# Amazing-All-Band-Receiver.net
KiCad netlist of a schematic drawn in EAGLE
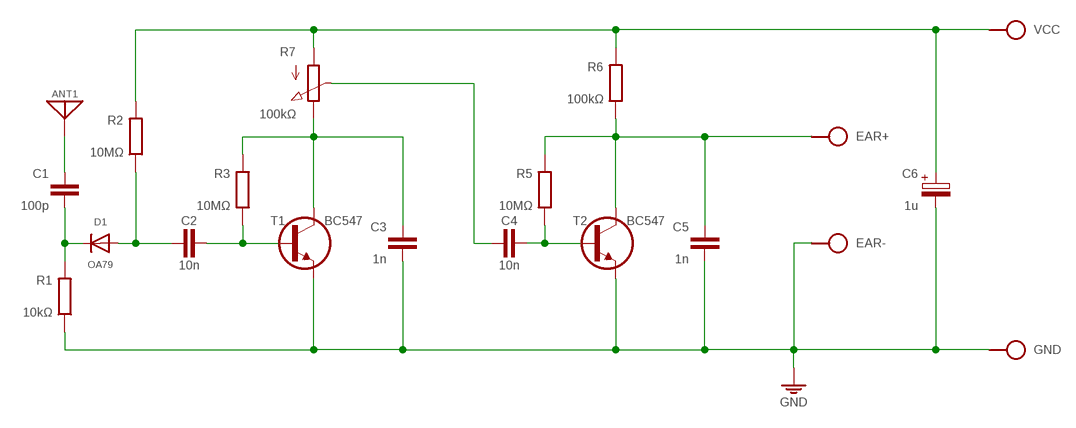
[diagram p0: schematic, sheet 1]

(export (version "E")
  (design (tool "Eeschema 10.0.6"))
  (components
    (comp (ref "ANT1")
      (value "ANT")
      (footprint "eagle-import:SPAD")
      (libsource (lib "eagle-import") (part "ANT"))
    )
    (comp (ref "C1")
      (value "100p")
      (footprint "eagle-import:C050-020X036_V")
      (libsource (lib "eagle-import") (part "C050-020X036/V"))
    )
    (comp (ref "C2")
      (value "10n")
      (footprint "eagle-import:C050-020X036")
      (libsource (lib "eagle-import") (part "C050-020X036"))
    )
    (comp (ref "C3")
      (value "1n")
      (footprint "eagle-import:C050-020X036")
      (libsource (lib "eagle-import") (part "C050-020X036"))
    )
    (comp (ref "C4")
      (value "10n")
      (footprint "eagle-import:C050-020X036")
      (libsource (lib "eagle-import") (part "C050-020X036"))
    )
    (comp (ref "C5")
      (value "1n")
      (footprint "eagle-import:C050-020X036")
      (libsource (lib "eagle-import") (part "C050-020X036"))
    )
    (comp (ref "C6")
      (value "1u")
      (footprint "eagle-import:E2,5-3")
      (libsource (lib "eagle-import") (part "CPOLE2,5-3"))
    )
    (comp (ref "D1")
      (value "OA79")
      (footprint "eagle-import:DO34-7V")
      (libsource (lib "eagle-import") (part "1N414834-7V"))
    )
    (comp (ref "EAR+")
      (value "SPAD")
      (footprint "eagle-import:SPAD")
      (libsource (lib "eagle-import") (part "SPAD"))
    )
    (comp (ref "EAR-")
      (value "SPAD")
      (footprint "eagle-import:SPAD")
      (libsource (lib "eagle-import") (part "SPAD"))
    )
    (comp (ref "GND")
      (value "SPAD")
      (footprint "eagle-import:SPAD")
      (libsource (lib "eagle-import") (part "SPAD"))
    )
    (comp (ref "R1")
      (value "10kΩ")
      (footprint "eagle-import:0202_7-V")
      (libsource (lib "eagle-import") (part "R0202/7-V"))
    )
    (comp (ref "R2")
      (value "10MΩ")
      (footprint "eagle-import:0202_7")
      (libsource (lib "eagle-import") (part "R0202/7"))
    )
    (comp (ref "R3")
      (value "10MΩ")
      (footprint "eagle-import:0202_7-V")
      (libsource (lib "eagle-import") (part "R0202/7-V"))
    )
    (comp (ref "R5")
      (value "10MΩ")
      (footprint "eagle-import:0202_7-V")
      (libsource (lib "eagle-import") (part "R0202/7-V"))
    )
    (comp (ref "R6")
      (value "100kΩ")
      (footprint "eagle-import:0202_7-V")
      (libsource (lib "eagle-import") (part "R0202/7-V"))
    )
    (comp (ref "R7")
      (value "100kΩ")
      (footprint "eagle-import:POT")
      (libsource (lib "eagle-import") (part "POT"))
    )
    (comp (ref "T1")
      (value "BC547")
      (footprint "eagle-import:TO92-CBE")
      (libsource (lib "eagle-import") (part "BC547CBE"))
    )
    (comp (ref "T2")
      (value "BC547")
      (footprint "eagle-import:TO92-CBE")
      (libsource (lib "eagle-import") (part "BC547CBE"))
    )
    (comp (ref "VCC")
      (value "SPAD")
      (footprint "eagle-import:SPAD")
      (libsource (lib "eagle-import") (part "SPAD"))
    )
  )
  (nets
    (net (code "1") (name "GND") (class "Default")
      (node (ref "C3") (pin "2") (pinfunction "2_2") (pintype "passive"))
      (node (ref "C5") (pin "2") (pinfunction "2_2") (pintype "passive"))
      (node (ref "C6") (pin "-") (pinfunction "-_-") (pintype "passive"))
      (node (ref "EAR-") (pin "1") (pinfunction "P$1_1") (pintype "bidirectional"))
      (node (ref "GND") (pin "1") (pinfunction "P$1_1") (pintype "bidirectional"))
      (node (ref "R1") (pin "1") (pinfunction "1_1") (pintype "passive"))
      (node (ref "T1") (pin "E") (pinfunction "E_E") (pintype "passive"))
      (node (ref "T2") (pin "E") (pinfunction "E_E") (pintype "passive"))
    )
    (net (code "2") (name "Net-(ANT1-Pad1)") (class "Default")
      (node (ref "ANT1") (pin "1") (pinfunction "1_1") (pintype "output"))
      (node (ref "C1") (pin "1") (pinfunction "1_1") (pintype "passive"))
    )
    (net (code "3") (name "Net-(C1-Pad2)") (class "Default")
      (node (ref "C1") (pin "2") (pinfunction "2_2") (pintype "passive"))
      (node (ref "D1") (pin "C") (pinfunction "C_C") (pintype "passive"))
      (node (ref "R1") (pin "2") (pinfunction "2_2") (pintype "passive"))
    )
    (net (code "4") (name "Net-(C2-Pad1)") (class "Default")
      (node (ref "C2") (pin "1") (pinfunction "1_1") (pintype "passive"))
      (node (ref "R3") (pin "1") (pinfunction "1_1") (pintype "passive"))
      (node (ref "T1") (pin "B") (pinfunction "B_B") (pintype "passive"))
    )
    (net (code "5") (name "Net-(C2-Pad2)") (class "Default")
      (node (ref "C2") (pin "2") (pinfunction "2_2") (pintype "passive"))
      (node (ref "D1") (pin "A") (pinfunction "A_A") (pintype "passive"))
      (node (ref "R2") (pin "1") (pinfunction "1_1") (pintype "passive"))
    )
    (net (code "6") (name "Net-(C4-Pad1)") (class "Default")
      (node (ref "C4") (pin "1") (pinfunction "1_1") (pintype "passive"))
      (node (ref "R5") (pin "1") (pinfunction "1_1") (pintype "passive"))
      (node (ref "T2") (pin "B") (pinfunction "B_B") (pintype "passive"))
    )
    (net (code "7") (name "Net-(EAR+-P$1)") (class "Default")
      (node (ref "C5") (pin "1") (pinfunction "1_1") (pintype "passive"))
      (node (ref "EAR+") (pin "1") (pinfunction "P$1_1") (pintype "bidirectional"))
      (node (ref "R5") (pin "2") (pinfunction "2_2") (pintype "passive"))
      (node (ref "R6") (pin "1") (pinfunction "1_1") (pintype "passive"))
      (node (ref "T2") (pin "C") (pinfunction "C_C") (pintype "passive"))
    )
    (net (code "8") (name "Net-(R7-A)") (class "Default")
      (node (ref "C6") (pin "+") (pinfunction "+_+") (pintype "passive"))
      (node (ref "R2") (pin "2") (pinfunction "2_2") (pintype "passive"))
      (node (ref "R6") (pin "2") (pinfunction "2_2") (pintype "passive"))
      (node (ref "R7") (pin "1") (pinfunction "A_1") (pintype "passive"))
      (node (ref "VCC") (pin "1") (pinfunction "P$1_1") (pintype "bidirectional"))
    )
    (net (code "9") (name "Net-(R7-E)") (class "Default")
      (node (ref "C3") (pin "1") (pinfunction "1_1") (pintype "passive"))
      (node (ref "R3") (pin "2") (pinfunction "2_2") (pintype "passive"))
      (node (ref "R7") (pin "3") (pinfunction "E_3") (pintype "passive"))
      (node (ref "T1") (pin "C") (pinfunction "C_C") (pintype "passive"))
    )
    (net (code "10") (name "Net-(R7-S)") (class "Default")
      (node (ref "C4") (pin "2") (pinfunction "2_2") (pintype "passive"))
      (node (ref "R7") (pin "2") (pinfunction "S_2") (pintype "passive"))
    )
  )
)
